# design.net
KiCad netlist of a schematic drawn in Altium Designer
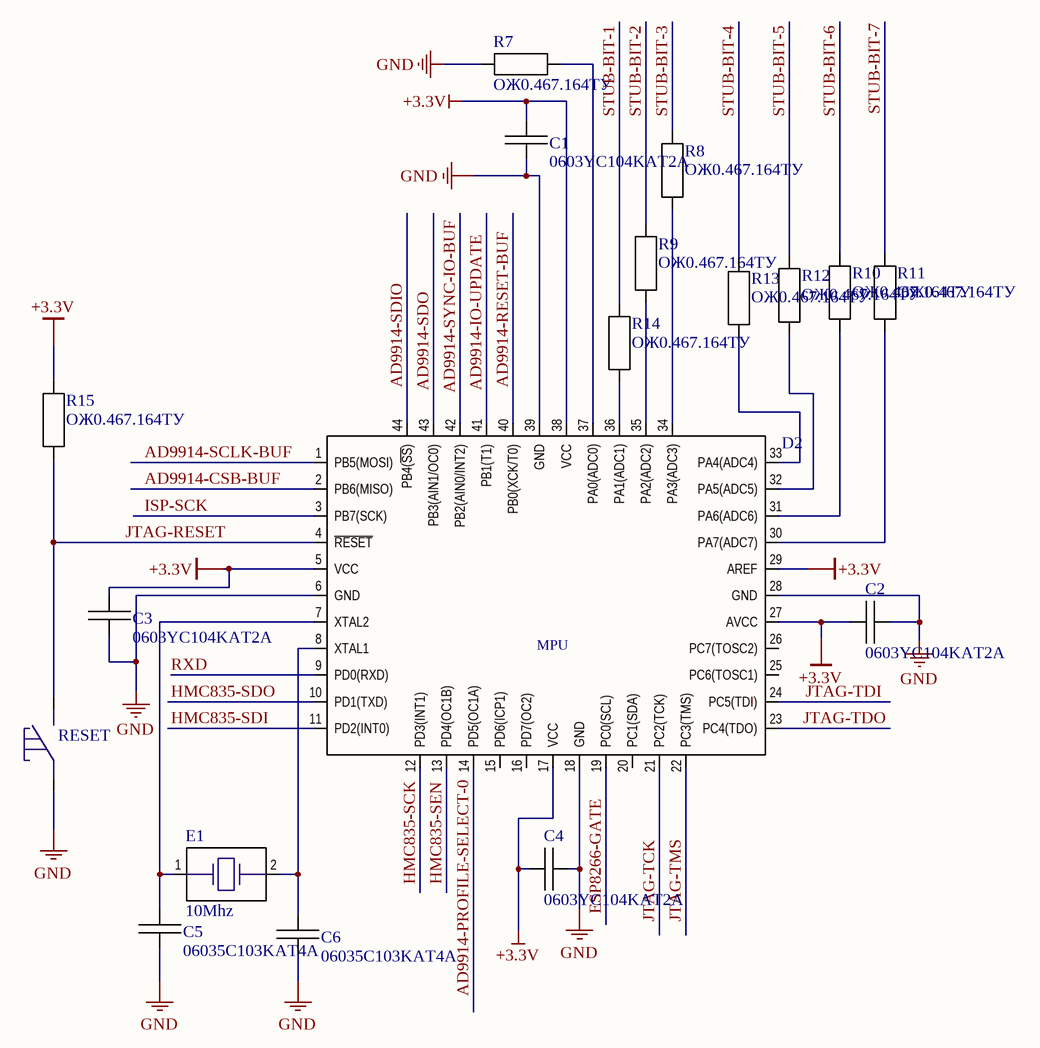
[diagram p0: Контроллер.SchDoc]

(export (version "E")
  (design (tool "Eeschema 10.0.6"))
  (components
    (comp (ref "C1")
      (value "0603YC104KAT2A")
      (footprint "0603-AVX")
      (fields (field (name "MANUFACTURER") "AVX") (field (name "TOLERANCE") "±10%"))
      (libsource (lib "КОНДЕНСАТОРЫ") (part "0603-X7R-0,1мкФ-16В-10%"))
    )
    (comp (ref "C2")
      (value "0603YC104KAT2A")
      (footprint "0603-AVX")
      (fields (field (name "MANUFACTURER") "AVX") (field (name "TOLERANCE") "±10%"))
      (libsource (lib "КОНДЕНСАТОРЫ") (part "0603-X7R-0,1мкФ-16В-10%"))
    )
    (comp (ref "C3")
      (value "0603YC104KAT2A")
      (footprint "0603-AVX")
      (fields (field (name "MANUFACTURER") "AVX") (field (name "TOLERANCE") "±10%"))
      (libsource (lib "КОНДЕНСАТОРЫ") (part "0603-X7R-0,1мкФ-16В-10%"))
    )
    (comp (ref "C4")
      (value "0603YC104KAT2A")
      (footprint "0603-AVX")
      (fields (field (name "MANUFACTURER") "AVX") (field (name "TOLERANCE") "±10%"))
      (libsource (lib "КОНДЕНСАТОРЫ") (part "0603-X7R-0,1мкФ-16В-10%"))
    )
    (comp (ref "C5")
      (value "06035C103KAT4A")
      (footprint "0603-AVX")
      (fields (field (name "MANUFACTURER") "AVX") (field (name "TOLERANCE") "±10%"))
      (libsource (lib "КОНДЕНСАТОРЫ") (part "0603-X7R-0,01мкФ-50В-10%"))
    )
    (comp (ref "C6")
      (value "06035C103KAT4A")
      (footprint "0603-AVX")
      (fields (field (name "MANUFACTURER") "AVX") (field (name "TOLERANCE") "±10%"))
      (libsource (lib "КОНДЕНСАТОРЫ") (part "0603-X7R-0,01мкФ-50В-10%"))
    )
    (comp (ref "D2")
      (value "~")
      (footprint "LQFP-44")
      (description "AVR 8-bit microcontroller")
      (fields (field (name "MANUFACTURER") "Atmel") (field (name "MANUFACTURERPARTNUMBER") "ATmega16"))
      (libsource (lib "МИКРОСХЕМЫ") (part "ATmega16"))
    )
    (comp (ref "E1")
      (value "10Mhz")
      (footprint "HC49")
      (fields (field (name "MANUFACTURERPARTNUMBER") "Crystal oscillator 16Mhz"))
      (libsource (lib "МИКРОСХЕМЫ") (part "Crystal oscillator 16Mhz"))
    )
    (comp (ref "R7")
      (value "ОЖ0.467.164ТУ")
      (footprint "Р1-8МП-0,125")
      (fields
        (field (name "TOLERANCE") "±1%-0,5-Л")
        (field (name "MANUFACTURERPARTNUMBER") "Р1-8МП-0,125-100 Ом±1%-0,5-Л")
      )
      (libsource (lib "РЕЗИСТОРЫ") (part "Р1-8МП-0,125-100 Ом±1%"))
    )
    (comp (ref "R8")
      (value "ОЖ0.467.164ТУ")
      (footprint "Р1-8МП-0,125")
      (fields
        (field (name "TOLERANCE") "±1%-0,5-Л")
        (field (name "MANUFACTURERPARTNUMBER") "Р1-8МП-0,125-100 Ом±1%-0,5-Л")
      )
      (libsource (lib "РЕЗИСТОРЫ") (part "Р1-8МП-0,125-100 Ом±1%"))
    )
    (comp (ref "R9")
      (value "ОЖ0.467.164ТУ")
      (footprint "Р1-8МП-0,125")
      (fields
        (field (name "TOLERANCE") "±1%-0,5-Л")
        (field (name "MANUFACTURERPARTNUMBER") "Р1-8МП-0,125-100 Ом±1%-0,5-Л")
      )
      (libsource (lib "РЕЗИСТОРЫ") (part "Р1-8МП-0,125-100 Ом±1%"))
    )
    (comp (ref "R10")
      (value "ОЖ0.467.164ТУ")
      (footprint "Р1-8МП-0,125")
      (fields
        (field (name "TOLERANCE") "±1%-0,5-Л")
        (field (name "MANUFACTURERPARTNUMBER") "Р1-8МП-0,125-100 Ом±1%-0,5-Л")
      )
      (libsource (lib "РЕЗИСТОРЫ") (part "Р1-8МП-0,125-100 Ом±1%"))
    )
    (comp (ref "R11")
      (value "ОЖ0.467.164ТУ")
      (footprint "Р1-8МП-0,125")
      (fields
        (field (name "TOLERANCE") "±1%-0,5-Л")
        (field (name "MANUFACTURERPARTNUMBER") "Р1-8МП-0,125-100 Ом±1%-0,5-Л")
      )
      (libsource (lib "РЕЗИСТОРЫ") (part "Р1-8МП-0,125-100 Ом±1%"))
    )
    (comp (ref "R12")
      (value "ОЖ0.467.164ТУ")
      (footprint "Р1-8МП-0,125")
      (fields
        (field (name "TOLERANCE") "±1%-0,5-Л")
        (field (name "MANUFACTURERPARTNUMBER") "Р1-8МП-0,125-100 Ом±1%-0,5-Л")
      )
      (libsource (lib "РЕЗИСТОРЫ") (part "Р1-8МП-0,125-100 Ом±1%"))
    )
    (comp (ref "R13")
      (value "ОЖ0.467.164ТУ")
      (footprint "Р1-8МП-0,125")
      (fields
        (field (name "TOLERANCE") "±1%-0,5-Л")
        (field (name "MANUFACTURERPARTNUMBER") "Р1-8МП-0,125-100 Ом±1%-0,5-Л")
      )
      (libsource (lib "РЕЗИСТОРЫ") (part "Р1-8МП-0,125-100 Ом±1%"))
    )
    (comp (ref "R14")
      (value "ОЖ0.467.164ТУ")
      (footprint "Р1-8МП-0,125")
      (fields
        (field (name "TOLERANCE") "±1%-0,5-Л")
        (field (name "MANUFACTURERPARTNUMBER") "Р1-8МП-0,125-100 Ом±1%-0,5-Л")
      )
      (libsource (lib "РЕЗИСТОРЫ") (part "Р1-8МП-0,125-100 Ом±1%"))
    )
    (comp (ref "R15")
      (value "ОЖ0.467.164ТУ")
      (footprint "Р1-8МП-0,125")
      (fields
        (field (name "TOLERANCE") "±1%-0,5-Л")
        (field (name "MANUFACTURERPARTNUMBER") "Р1-8МП-0,125-100 Ом±1%-0,5-Л")
      )
      (libsource (lib "РЕЗИСТОРЫ") (part "Р1-8МП-0,125-100 Ом±1%"))
    )
    (comp (ref "RESET")
      (value "Кнопка тактовая smd")
      (footprint "Кнопка тактовая smd")
      (libsource (lib "РАЗЪЕМЫ") (part "Кнопка тактовая smd"))
    )
  )
  (nets
    (net (code "1") (name "+3.3V") (class "Default")
      (node (ref "C1") (pin "1") (pinfunction "1_1") (pintype "passive"))
      (node (ref "C2") (pin "2") (pinfunction "2_2") (pintype "passive"))
      (node (ref "C3") (pin "2") (pinfunction "2_2") (pintype "passive"))
      (node (ref "C4") (pin "2") (pinfunction "2_2") (pintype "passive"))
      (node (ref "D2") (pin "17") (pinfunction "VCC_17") (pintype "passive"))
      (node (ref "D2") (pin "27") (pinfunction "AVCC_27") (pintype "passive"))
      (node (ref "D2") (pin "29") (pinfunction "AREF_29") (pintype "passive"))
      (node (ref "D2") (pin "38") (pinfunction "VCC_38") (pintype "passive"))
      (node (ref "D2") (pin "5") (pinfunction "VCC_5") (pintype "passive"))
      (node (ref "R15") (pin "1") (pinfunction "1_1") (pintype "passive"))
    )
    (net (code "2") (name "/AD9914-CSB-BUF") (class "Default")
      (node (ref "D2") (pin "2") (pinfunction "PB6(MISO)_2") (pintype "passive"))
    )
    (net (code "3") (name "/AD9914-IO-UPDATE") (class "Default")
      (node (ref "D2") (pin "41") (pinfunction "PB1(T1)_41") (pintype "passive"))
    )
    (net (code "4") (name "/AD9914-PROFILE-SELECT-0") (class "Default")
      (node (ref "D2") (pin "14") (pinfunction "PD5(OC1A)_14") (pintype "passive"))
    )
    (net (code "5") (name "/AD9914-RESET-BUF") (class "Default")
      (node (ref "D2") (pin "40") (pinfunction "PB0(XCK/T0)_40") (pintype "passive"))
    )
    (net (code "6") (name "/AD9914-SCLK-BUF") (class "Default")
      (node (ref "D2") (pin "1") (pinfunction "PB5(MOSI)_1") (pintype "passive"))
    )
    (net (code "7") (name "/AD9914-SDIO") (class "Default")
      (node (ref "D2") (pin "44") (pinfunction "PB4(~{SS})_44") (pintype "passive"))
    )
    (net (code "8") (name "/AD9914-SDO") (class "Default")
      (node (ref "D2") (pin "43") (pinfunction "PB3(AIN1/OC0)_43") (pintype "passive"))
    )
    (net (code "9") (name "/AD9914-SYNC-IO-BUF") (class "Default")
      (node (ref "D2") (pin "42") (pinfunction "PB2(AIN0/INT2)_42") (pintype "passive"))
    )
    (net (code "10") (name "/ESP8266-GATE") (class "Default")
      (node (ref "D2") (pin "19") (pinfunction "PC0(SCL)_19") (pintype "passive"))
    )
    (net (code "11") (name "/HMC835-SCK") (class "Default")
      (node (ref "D2") (pin "12") (pinfunction "PD3(INT1)_12") (pintype "passive"))
    )
    (net (code "12") (name "/HMC835-SDI") (class "Default")
      (node (ref "D2") (pin "11") (pinfunction "PD2(INT0)_11") (pintype "passive"))
    )
    (net (code "13") (name "/HMC835-SDO") (class "Default")
      (node (ref "D2") (pin "10") (pinfunction "PD1(TXD)_10") (pintype "passive"))
    )
    (net (code "14") (name "/HMC835-SEN") (class "Default")
      (node (ref "D2") (pin "13") (pinfunction "PD4(OC1B)_13") (pintype "passive"))
    )
    (net (code "15") (name "/ISP-SCK") (class "Default")
      (node (ref "D2") (pin "3") (pinfunction "PB7(SCK)_3") (pintype "passive"))
    )
    (net (code "16") (name "/JTAG-RESET") (class "Default")
      (node (ref "D2") (pin "4") (pinfunction "~{RESET}_4") (pintype "passive"))
      (node (ref "R15") (pin "2") (pinfunction "2_2") (pintype "passive"))
      (node (ref "RESET") (pin "3") (pinfunction "3_3") (pintype "passive"))
    )
    (net (code "17") (name "/JTAG-TCK") (class "Default")
      (node (ref "D2") (pin "21") (pinfunction "PC2(TCK)_21") (pintype "passive"))
    )
    (net (code "18") (name "/JTAG-TDI") (class "Default")
      (node (ref "D2") (pin "24") (pinfunction "PC5(TDI)_24") (pintype "passive"))
    )
    (net (code "19") (name "/JTAG-TDO") (class "Default")
      (node (ref "D2") (pin "23") (pinfunction "PC4(TDO)_23") (pintype "passive"))
    )
    (net (code "20") (name "/JTAG-TMS") (class "Default")
      (node (ref "D2") (pin "22") (pinfunction "PC3(TMS)_22") (pintype "passive"))
    )
    (net (code "21") (name "/RXD") (class "Default")
      (node (ref "D2") (pin "9") (pinfunction "PD0(RXD)_9") (pintype "passive"))
    )
    (net (code "22") (name "/STUB-BIT-1") (class "Default")
      (node (ref "R14") (pin "2") (pinfunction "2_2") (pintype "passive"))
    )
    (net (code "23") (name "/STUB-BIT-2") (class "Default")
      (node (ref "R9") (pin "2") (pinfunction "2_2") (pintype "passive"))
    )
    (net (code "24") (name "/STUB-BIT-3") (class "Default")
      (node (ref "R8") (pin "2") (pinfunction "2_2") (pintype "passive"))
    )
    (net (code "25") (name "/STUB-BIT-4") (class "Default")
      (node (ref "R13") (pin "2") (pinfunction "2_2") (pintype "passive"))
    )
    (net (code "26") (name "/STUB-BIT-5") (class "Default")
      (node (ref "R12") (pin "2") (pinfunction "2_2") (pintype "passive"))
    )
    (net (code "27") (name "/STUB-BIT-6") (class "Default")
      (node (ref "R10") (pin "2") (pinfunction "2_2") (pintype "passive"))
    )
    (net (code "28") (name "/STUB-BIT-7") (class "Default")
      (node (ref "R11") (pin "2") (pinfunction "2_2") (pintype "passive"))
    )
    (net (code "29") (name "1") (class "Default")
      (node (ref "RESET") (pin "2") (pinfunction "2_2") (pintype "passive"))
    )
    (net (code "30") (name "3") (class "Default")
      (node (ref "RESET") (pin "4") (pinfunction "4_4") (pintype "passive"))
    )
    (net (code "31") (name "GND") (class "Default")
      (node (ref "C1") (pin "2") (pinfunction "2_2") (pintype "passive"))
      (node (ref "C2") (pin "1") (pinfunction "1_1") (pintype "passive"))
      (node (ref "C3") (pin "1") (pinfunction "1_1") (pintype "passive"))
      (node (ref "C4") (pin "1") (pinfunction "1_1") (pintype "passive"))
      (node (ref "C5") (pin "1") (pinfunction "1_1") (pintype "passive"))
      (node (ref "C6") (pin "1") (pinfunction "1_1") (pintype "passive"))
      (node (ref "D2") (pin "18") (pinfunction "GND_18") (pintype "passive"))
      (node (ref "D2") (pin "28") (pinfunction "GND_28") (pintype "passive"))
      (node (ref "D2") (pin "39") (pinfunction "GND_39") (pintype "passive"))
      (node (ref "D2") (pin "6") (pinfunction "GND_6") (pintype "passive"))
      (node (ref "R7") (pin "1") (pinfunction "1_1") (pintype "passive"))
      (node (ref "RESET") (pin "1") (pinfunction "1_1") (pintype "passive"))
    )
    (net (code "32") (name "Net-(D2-PA0(ADC0))") (class "Default")
      (node (ref "D2") (pin "37") (pinfunction "PA0(ADC0)_37") (pintype "passive"))
      (node (ref "R7") (pin "2") (pinfunction "2_2") (pintype "passive"))
    )
    (net (code "33") (name "Net-(D2-PA1(ADC1))") (class "Default")
      (node (ref "D2") (pin "36") (pinfunction "PA1(ADC1)_36") (pintype "passive"))
      (node (ref "R14") (pin "1") (pinfunction "1_1") (pintype "passive"))
    )
    (net (code "34") (name "Net-(D2-PA2(ADC2))") (class "Default")
      (node (ref "D2") (pin "35") (pinfunction "PA2(ADC2)_35") (pintype "passive"))
      (node (ref "R9") (pin "1") (pinfunction "1_1") (pintype "passive"))
    )
    (net (code "35") (name "Net-(D2-PA3(ADC3))") (class "Default")
      (node (ref "D2") (pin "34") (pinfunction "PA3(ADC3)_34") (pintype "passive"))
      (node (ref "R8") (pin "1") (pinfunction "1_1") (pintype "passive"))
    )
    (net (code "36") (name "Net-(D2-PA4(ADC4))") (class "Default")
      (node (ref "D2") (pin "33") (pinfunction "PA4(ADC4)_33") (pintype "passive"))
      (node (ref "R13") (pin "1") (pinfunction "1_1") (pintype "passive"))
    )
    (net (code "37") (name "Net-(D2-PA5(ADC5))") (class "Default")
      (node (ref "D2") (pin "32") (pinfunction "PA5(ADC5)_32") (pintype "passive"))
      (node (ref "R12") (pin "1") (pinfunction "1_1") (pintype "passive"))
    )
    (net (code "38") (name "Net-(D2-PA6(ADC6))") (class "Default")
      (node (ref "D2") (pin "31") (pinfunction "PA6(ADC6)_31") (pintype "passive"))
      (node (ref "R10") (pin "1") (pinfunction "1_1") (pintype "passive"))
    )
    (net (code "39") (name "Net-(D2-PA7(ADC7))") (class "Default")
      (node (ref "D2") (pin "30") (pinfunction "PA7(ADC7)_30") (pintype "passive"))
      (node (ref "R11") (pin "1") (pinfunction "1_1") (pintype "passive"))
    )
    (net (code "40") (name "Net-(D2-XTAL1)") (class "Default")
      (node (ref "C6") (pin "2") (pinfunction "2_2") (pintype "passive"))
      (node (ref "D2") (pin "8") (pinfunction "XTAL1_8") (pintype "passive"))
      (node (ref "E1") (pin "2") (pintype "passive"))
    )
    (net (code "41") (name "Net-(D2-XTAL2)") (class "Default")
      (node (ref "C5") (pin "2") (pinfunction "2_2") (pintype "passive"))
      (node (ref "D2") (pin "7") (pinfunction "XTAL2_7") (pintype "passive"))
      (node (ref "E1") (pin "1") (pintype "passive"))
    )
    (net (code "42") (name "unconnected-(D2-PC1(SDA)-Pad20)") (class "Default")
      (node (ref "D2") (pin "20") (pinfunction "PC1(SDA)_20") (pintype "passive"))
    )
    (net (code "43") (name "unconnected-(D2-PC6(TOSC1)-Pad25)") (class "Default")
      (node (ref "D2") (pin "25") (pinfunction "PC6(TOSC1)_25") (pintype "passive"))
    )
    (net (code "44") (name "unconnected-(D2-PC7(TOSC2)-Pad26)") (class "Default")
      (node (ref "D2") (pin "26") (pinfunction "PC7(TOSC2)_26") (pintype "passive"))
    )
    (net (code "45") (name "unconnected-(D2-PD6(ICP1)-Pad15)") (class "Default")
      (node (ref "D2") (pin "15") (pinfunction "PD6(ICP1)_15") (pintype "passive"))
    )
    (net (code "46") (name "unconnected-(D2-PD7(OC2)-Pad16)") (class "Default")
      (node (ref "D2") (pin "16") (pinfunction "PD7(OC2)_16") (pintype "passive"))
    )
  )
)
